# POWER.net
KiCad netlist of a schematic drawn in Altium Designer
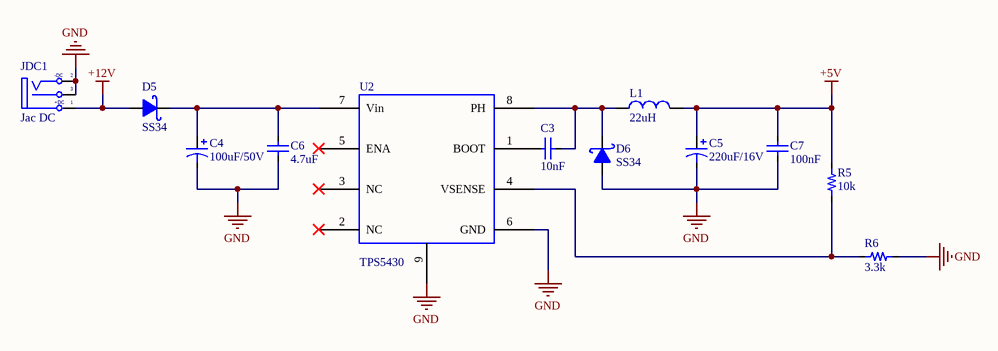
[diagram p0: POWER.SchDoc]

(export (version "E")
  (design (tool "Eeschema 10.0.6"))
  (components
    (comp (ref "C3")
      (value "10nF")
      (footprint "CAP_0805")
      (description "Capacitor")
      (fields (field (name "PUBLISHER") "Altium Limited"))
      (libsource (lib "My Library") (part "CapSMD"))
    )
    (comp (ref "C4")
      (value "100uF/50V")
      (footprint "C8mm")
      (description "Polarized Capacitor (Axial)")
      (fields (field (name "PUBLISHER") "Altium Limited"))
      (libsource (lib "My Library") (part "Cap Pol"))
    )
    (comp (ref "C5")
      (value "220uF/16V")
      (footprint "C5mm")
      (description "Polarized Capacitor (Axial)")
      (fields (field (name "PUBLISHER") "Altium Limited"))
      (libsource (lib "My Library") (part "Cap Pol"))
    )
    (comp (ref "C6")
      (value "4.7uF")
      (footprint "CAP_0805")
      (description "Capacitor")
      (fields (field (name "PUBLISHER") "Altium Limited"))
      (libsource (lib "My Library") (part "CapSMD"))
    )
    (comp (ref "C7")
      (value "100nF")
      (footprint "CAP_0805")
      (description "Capacitor")
      (fields (field (name "PUBLISHER") "Altium Limited"))
      (libsource (lib "My Library") (part "CapSMD"))
    )
    (comp (ref "D5")
      (value "SS34")
      (footprint "DIODE SMA")
      (description "Schottky Rectifiers")
      (libsource (lib "My Library") (part "1N5822"))
    )
    (comp (ref "D6")
      (value "SS34")
      (footprint "DIODE SMA")
      (description "Schottky Rectifiers")
      (libsource (lib "My Library") (part "1N5822"))
    )
    (comp (ref "JDC1")
      (value "Jac DC")
      (footprint "DC-IN")
      (description "Jac DC input")
      (libsource (lib "My Library") (part "DCIN"))
    )
    (comp (ref "L1")
      (value "22uH")
      (footprint "L_SMD")
      (description "CD73R 22uH 1.23A 7345")
      (libsource (lib "My Library") (part "Inductor"))
    )
    (comp (ref "R5")
      (value "10k")
      (footprint "RES-SMD-0805")
      (description "Resistor")
      (fields
        (field (name "MANUFACTURER") "Generic Components")
        (field (name "PUBLISHER") "Altium Hobart Technology Centre")
      )
      (libsource (lib "My Library") (part "Resistor - SMD"))
    )
    (comp (ref "R6")
      (value "3.3k")
      (footprint "RES-SMD-0805")
      (description "Resistor")
      (fields
        (field (name "MANUFACTURER") "Generic Components")
        (field (name "PUBLISHER") "Altium Hobart Technology Centre")
      )
      (libsource (lib "My Library") (part "Resistor - SMD"))
    )
    (comp (ref "U2")
      (value "TPS5430")
      (footprint "TPS5430-2")
      (fields (field (name "NAME") "TPS5430"))
      (libsource (lib "My Library") (part "TPS5430"))
    )
  )
  (nets
    (net (code "1") (name "+5V") (class "Default")
      (node (ref "C5") (pin "1") (pinfunction "1_1") (pintype "passive"))
      (node (ref "C7") (pin "1") (pinfunction "1_1") (pintype "passive"))
      (node (ref "L1") (pin "2") (pinfunction "2_2") (pintype "passive"))
      (node (ref "R5") (pin "2") (pinfunction "2_2") (pintype "passive"))
    )
    (net (code "2") (name "+12V") (class "Default")
      (node (ref "D5") (pin "1") (pinfunction "A_1") (pintype "passive"))
      (node (ref "JDC1") (pin "1") (pinfunction "T_1") (pintype "passive"))
    )
    (net (code "3") (name "GND") (class "Default")
      (node (ref "C4") (pin "2") (pinfunction "2_2") (pintype "passive"))
      (node (ref "C5") (pin "2") (pinfunction "2_2") (pintype "passive"))
      (node (ref "C6") (pin "2") (pinfunction "2_2") (pintype "passive"))
      (node (ref "C7") (pin "2") (pinfunction "2_2") (pintype "passive"))
      (node (ref "D6") (pin "1") (pinfunction "A_1") (pintype "passive"))
      (node (ref "JDC1") (pin "2") (pinfunction "TN_2") (pintype "passive"))
      (node (ref "JDC1") (pin "3") (pinfunction "S_3") (pintype "power_in"))
      (node (ref "R6") (pin "2") (pinfunction "2_2") (pintype "passive"))
      (node (ref "U2") (pin "6") (pinfunction "GND_6") (pintype "passive"))
      (node (ref "U2") (pin "9") (pinfunction "PWR_PAD_9") (pintype "passive"))
    )
    (net (code "4") (name "Net-(D5-K)") (class "Default")
      (node (ref "C4") (pin "1") (pinfunction "1_1") (pintype "passive"))
      (node (ref "C6") (pin "1") (pinfunction "1_1") (pintype "passive"))
      (node (ref "D5") (pin "2") (pinfunction "K_2") (pintype "passive"))
      (node (ref "U2") (pin "7") (pinfunction "Vin_7") (pintype "passive"))
    )
    (net (code "5") (name "Net-(D6-K)") (class "Default")
      (node (ref "C3") (pin "2") (pinfunction "2_2") (pintype "passive"))
      (node (ref "D6") (pin "2") (pinfunction "K_2") (pintype "passive"))
      (node (ref "L1") (pin "1") (pinfunction "1_1") (pintype "passive"))
      (node (ref "U2") (pin "8") (pinfunction "PH_8") (pintype "passive"))
    )
    (net (code "6") (name "Net-(U2-BOOT)") (class "Default")
      (node (ref "C3") (pin "1") (pinfunction "1_1") (pintype "passive"))
      (node (ref "U2") (pin "1") (pinfunction "BOOT_1") (pintype "passive"))
    )
    (net (code "7") (name "Net-(U2-VSENSE)") (class "Default")
      (node (ref "R5") (pin "1") (pinfunction "1_1") (pintype "passive"))
      (node (ref "R6") (pin "1") (pinfunction "1_1") (pintype "passive"))
      (node (ref "U2") (pin "4") (pinfunction "VSENSE_4") (pintype "passive"))
    )
    (net (code "8") (name "unconnected-(U2-ENA-Pad5)") (class "Default")
      (node (ref "U2") (pin "5") (pinfunction "ENA_5") (pintype "passive+no_connect"))
    )
    (net (code "9") (name "unconnected-(U2-NC-Pad2)") (class "Default")
      (node (ref "U2") (pin "2") (pinfunction "NC_2") (pintype "passive+no_connect"))
    )
    (net (code "10") (name "unconnected-(U2-NC-Pad3)") (class "Default")
      (node (ref "U2") (pin "3") (pinfunction "NC_3") (pintype "passive+no_connect"))
    )
  )
)
